# LCmeter0-LCD-8pinlcd.net
KiCad netlist of a schematic drawn in EAGLE
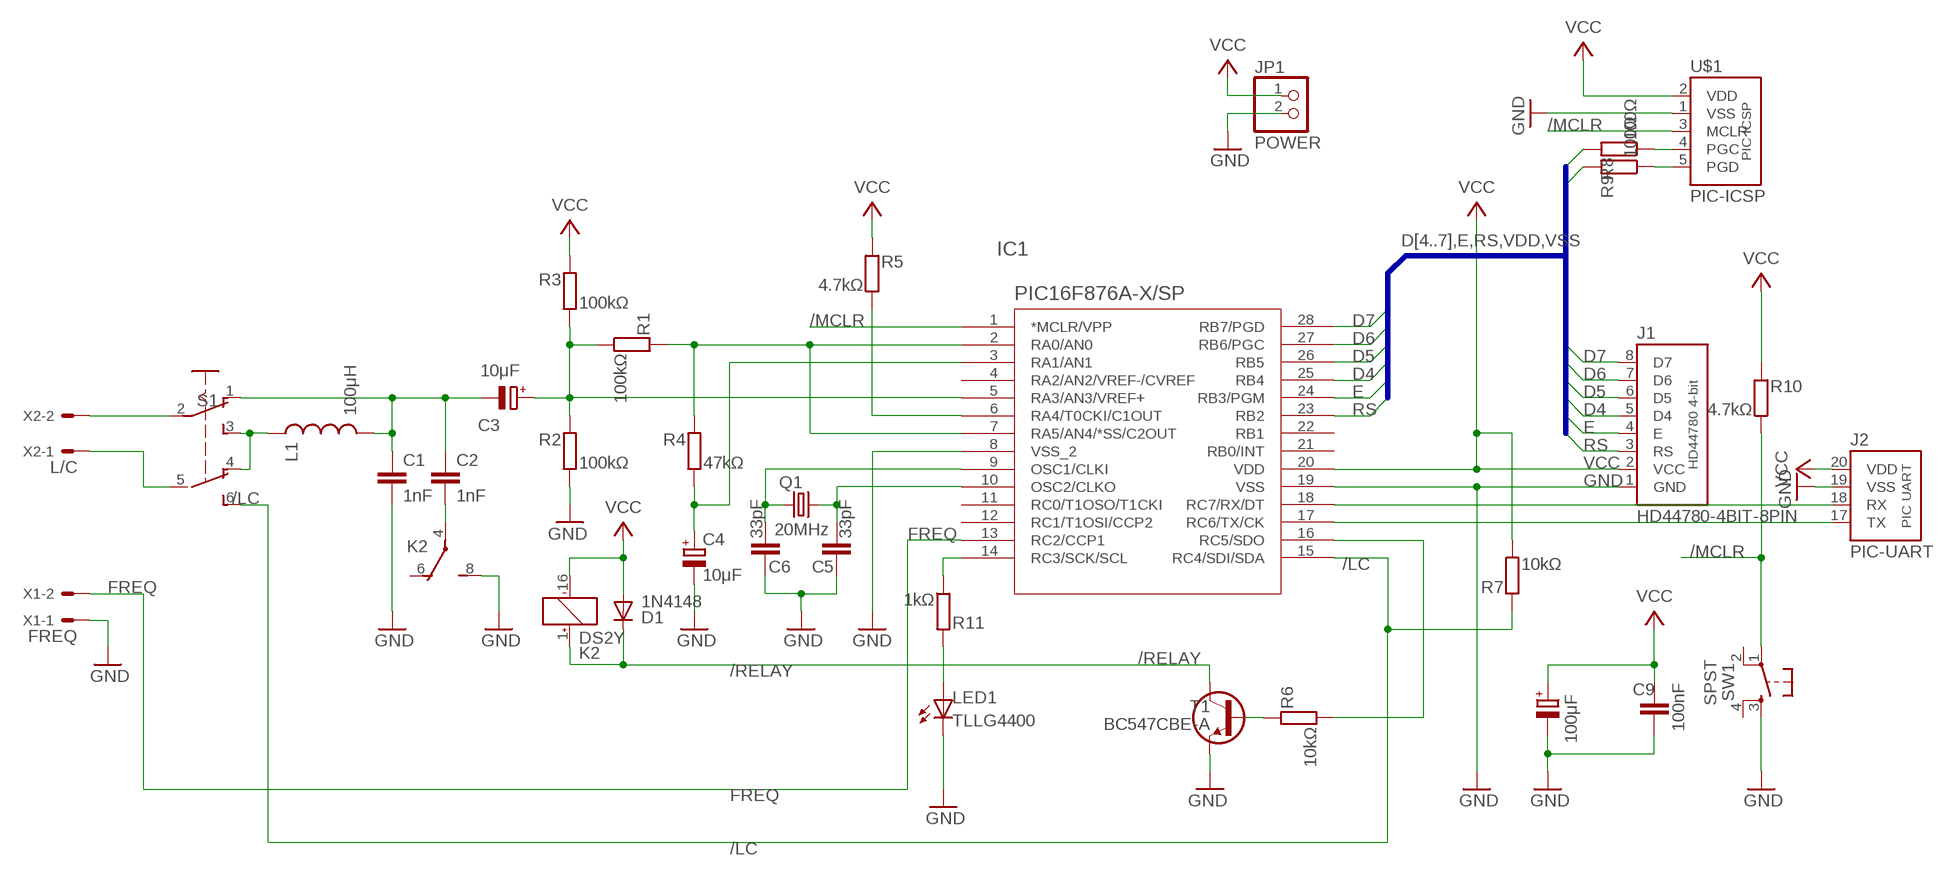
[diagram p0: schematic, sheet 1]

(export (version "E")
  (design (tool "Eeschema 10.0.6"))
  (components
    (comp (ref "C1")
      (value "1nF")
      (footprint "eagle-import:C050-020X036")
      (libsource (lib "eagle-import") (part "C050-020X036"))
    )
    (comp (ref "C2")
      (value "1nF")
      (footprint "eagle-import:C050-020X036")
      (libsource (lib "eagle-import") (part "C050-020X036"))
    )
    (comp (ref "C3")
      (value "10μF")
      (footprint "eagle-import:E5-4")
      (libsource (lib "eagle-import") (part "CPOLE5-4"))
    )
    (comp (ref "C4")
      (value "10μF")
      (footprint "eagle-import:E5-4")
      (libsource (lib "eagle-import") (part "CPOLE5-4"))
    )
    (comp (ref "C5")
      (value "33pF")
      (footprint "eagle-import:C025-020X036")
      (libsource (lib "eagle-import") (part "C025-020X036"))
    )
    (comp (ref "C6")
      (value "33pF")
      (footprint "eagle-import:C025-020X036")
      (libsource (lib "eagle-import") (part "C025-020X036"))
    )
    (comp (ref "C7")
      (value "100μF")
      (footprint "eagle-import:E2,5-6")
      (libsource (lib "eagle-import") (part "CPOLE2.5-6"))
    )
    (comp (ref "C9")
      (value "100nF")
      (footprint "eagle-import:C025-024X044")
      (libsource (lib "eagle-import") (part "C-EU025-024X044"))
    )
    (comp (ref "D1")
      (value "1N4148")
      (footprint "eagle-import:DO34-7")
      (libsource (lib "eagle-import") (part "1N414834-7"))
    )
    (comp (ref "IC1")
      (value "PIC16F876A-X/SP")
      (footprint "eagle-import:DIL28-3")
      (libsource (lib "eagle-import") (part "PIC16F876A-X/SP"))
    )
    (comp (ref "J1")
      (value "HD44780-4BIT-8PIN")
      (footprint "eagle-import:CONN-8P")
      (libsource (lib "eagle-import") (part "HD44780-4BIT-8PIN"))
    )
    (comp (ref "J2")
      (value "PIC-UART")
      (footprint "eagle-import:PIC-UART")
      (libsource (lib "eagle-import") (part "PIC-UART"))
    )
    (comp (ref "JP1")
      (value "POWER")
      (footprint "eagle-import:1X02")
      (libsource (lib "eagle-import") (part "PINHD-1X2"))
    )
    (comp (ref "K2")
      (value "DS2Y")
      (footprint "eagle-import:DS2Y")
      (fields (field (name "MPN") "DS2Y-S-DC5V"))
      (libsource (lib "eagle-import") (part "DS2Y-S-DC5V"))
    )
    (comp (ref "L1")
      (value "100μH")
      (footprint "eagle-import:L-02_7")
      (libsource (lib "eagle-import") (part "L02/7"))
    )
    (comp (ref "LED1")
      (value "TLLG4400")
      (footprint "eagle-import:LED3MM")
      (fields (field (name "MF") "VISHAY SEMICONDUCTOR"))
      (libsource (lib "eagle-import") (part "TLLG4400"))
    )
    (comp (ref "Q1")
      (value "20MHz")
      (footprint "eagle-import:HC49")
      (libsource (lib "eagle-import") (part "CRYSTALHC49"))
    )
    (comp (ref "R1")
      (value "100kΩ")
      (footprint "eagle-import:0202_2V")
      (libsource (lib "eagle-import") (part "R0202/2V"))
    )
    (comp (ref "R2")
      (value "100kΩ")
      (footprint "eagle-import:0202_7")
      (libsource (lib "eagle-import") (part "R0202/7"))
    )
    (comp (ref "R3")
      (value "100kΩ")
      (footprint "eagle-import:0202_2V")
      (libsource (lib "eagle-import") (part "R0202/2V"))
    )
    (comp (ref "R4")
      (value "47kΩ")
      (footprint "eagle-import:0202_2V")
      (libsource (lib "eagle-import") (part "R0202/2V"))
    )
    (comp (ref "R5")
      (value "4.7kΩ")
      (footprint "eagle-import:0202_7")
      (libsource (lib "eagle-import") (part "R0202/7"))
    )
    (comp (ref "R6")
      (value "10kΩ")
      (footprint "eagle-import:0202_7")
      (libsource (lib "eagle-import") (part "R0202/7"))
    )
    (comp (ref "R7")
      (value "10kΩ")
      (footprint "eagle-import:0202_10")
      (libsource (lib "eagle-import") (part "R0202/10"))
    )
    (comp (ref "R8")
      (value "100Ω")
      (footprint "eagle-import:0202_5")
      (libsource (lib "eagle-import") (part "R0202/5"))
    )
    (comp (ref "R9")
      (value "100Ω")
      (footprint "eagle-import:0202_5")
      (libsource (lib "eagle-import") (part "R0202/5"))
    )
    (comp (ref "R10")
      (value "4.7kΩ")
      (footprint "eagle-import:0202_2V")
      (libsource (lib "eagle-import") (part "R0202/2V"))
    )
    (comp (ref "R11")
      (value "1kΩ")
      (footprint "eagle-import:0202_5")
      (libsource (lib "eagle-import") (part "R0202/5"))
    )
    (comp (ref "S1")
      (value "SL-SW-2P-2T")
      (footprint "eagle-import:SLSW-2P2T")
      (libsource (lib "eagle-import") (part "SL-SW-2P-2T"))
    )
    (comp (ref "SW1")
      (value "SPST")
      (footprint "eagle-import:PB-5")
      (libsource (lib "eagle-import") (part "PB-SPST"))
    )
    (comp (ref "T1")
      (value "BC547CBE-A")
      (footprint "eagle-import:TO92-CBE-A")
      (libsource (lib "eagle-import") (part "BC547CBE-A"))
    )
    (comp (ref "U$1")
      (value "PIC-ICSP")
      (footprint "eagle-import:CONN-5P")
      (libsource (lib "eagle-import") (part "PIC-ICSP"))
    )
    (comp (ref "X1")
      (value "FREQ")
      (footprint "eagle-import:70543-02")
      (libsource (lib "eagle-import") (part "C-GRID-02-70543"))
    )
    (comp (ref "X2")
      (value "L/C")
      (footprint "eagle-import:70543-02")
      (libsource (lib "eagle-import") (part "C-GRID-02-70543"))
    )
  )
  (nets
    (net (code "3") (name "/D4") (class "Default")
      (node (ref "IC1") (pin "25") (pinfunction "RB4_25") (pintype "passive"))
      (node (ref "J1") (pin "5") (pinfunction "D4_5") (pintype "passive"))
    )
    (net (code "4") (name "/D5") (class "Default")
      (node (ref "IC1") (pin "26") (pinfunction "RB5_26") (pintype "passive"))
      (node (ref "J1") (pin "6") (pinfunction "D5_6") (pintype "passive"))
    )
    (net (code "5") (name "/D6") (class "Default")
      (node (ref "IC1") (pin "27") (pinfunction "RB6/PGC_27") (pintype "passive"))
      (node (ref "J1") (pin "7") (pinfunction "D6_7") (pintype "passive"))
      (node (ref "R9") (pin "2") (pinfunction "2_2") (pintype "passive"))
    )
    (net (code "6") (name "/D7") (class "Default")
      (node (ref "IC1") (pin "28") (pinfunction "RB7/PGD_28") (pintype "passive"))
      (node (ref "J1") (pin "8") (pinfunction "D7_8") (pintype "passive"))
      (node (ref "R8") (pin "2") (pinfunction "2_2") (pintype "passive"))
    )
    (net (code "7") (name "/E") (class "Default")
      (node (ref "IC1") (pin "24") (pinfunction "RB3/PGM_24") (pintype "passive"))
      (node (ref "J1") (pin "4") (pinfunction "E_4") (pintype "passive"))
    )
    (net (code "8") (name "/FREQ") (class "Default")
      (node (ref "IC1") (pin "13") (pinfunction "RC2/CCP1_13") (pintype "passive"))
      (node (ref "X1") (pin "2") (pinfunction "S_2") (pintype "passive"))
    )
    (net (code "9") (name "/RS") (class "Default")
      (node (ref "IC1") (pin "23") (pinfunction "RB2_23") (pintype "passive"))
      (node (ref "J1") (pin "3") (pinfunction "RS_3") (pintype "passive"))
    )
    (net (code "11") (name "/{slash}LC") (class "Default")
      (node (ref "IC1") (pin "15") (pinfunction "RC4/SDI/SDA_15") (pintype "passive"))
      (node (ref "R7") (pin "2") (pinfunction "2_2") (pintype "passive"))
      (node (ref "S1") (pin "6") (pinfunction "S1_6") (pintype "passive"))
    )
    (net (code "12") (name "/{slash}MCLR") (class "Default")
      (node (ref "IC1") (pin "1") (pinfunction "*MCLR/VPP_1") (pintype "passive"))
      (node (ref "R10") (pin "1") (pinfunction "1_1") (pintype "passive"))
      (node (ref "SW1") (pin "1") (pinfunction "P_1") (pintype "passive"))
      (node (ref "U$1") (pin "3") (pinfunction "MCLR_3") (pintype "passive"))
    )
    (net (code "13") (name "/{slash}RELAY") (class "Default")
      (node (ref "D1") (pin "C") (pinfunction "C_C") (pintype "passive"))
      (node (ref "K2") (pin "1") (pinfunction "+_1") (pintype "passive"))
      (node (ref "T1") (pin "C") (pinfunction "C_C") (pintype "passive"))
    )
    (net (code "14") (name "GND") (class "Default")
      (node (ref "C1") (pin "2") (pinfunction "2_2") (pintype "passive"))
      (node (ref "C4") (pin "-") (pinfunction "-_-") (pintype "passive"))
      (node (ref "C5") (pin "1") (pinfunction "1_1") (pintype "passive"))
      (node (ref "C6") (pin "1") (pinfunction "1_1") (pintype "passive"))
      (node (ref "C7") (pin "-") (pinfunction "-_-") (pintype "passive"))
      (node (ref "C9") (pin "2") (pinfunction "2_2") (pintype "passive"))
      (node (ref "IC1") (pin "19") (pinfunction "VSS_19") (pintype "passive"))
      (node (ref "IC1") (pin "8") (pinfunction "VSS_2_8") (pintype "passive"))
      (node (ref "J1") (pin "1") (pinfunction "GND_1") (pintype "passive"))
      (node (ref "J2") (pin "19") (pinfunction "VSS_19") (pintype "passive"))
      (node (ref "JP1") (pin "2") (pinfunction "2_2") (pintype "passive"))
      (node (ref "K2") (pin "8") (pinfunction "S_8") (pintype "passive"))
      (node (ref "LED1") (pin "K") (pinfunction "C_K") (pintype "passive"))
      (node (ref "R2") (pin "1") (pinfunction "1_1") (pintype "passive"))
      (node (ref "SW1") (pin "3") (pinfunction "S_3") (pintype "passive"))
      (node (ref "T1") (pin "E") (pinfunction "E_E") (pintype "passive"))
      (node (ref "U$1") (pin "1") (pinfunction "VSS_1") (pintype "passive"))
      (node (ref "X1") (pin "1") (pinfunction "S_1") (pintype "passive"))
    )
    (net (code "15") (name "Net-(IC1-OSC1{slash}CLKI)") (class "Default")
      (node (ref "C6") (pin "2") (pinfunction "2_2") (pintype "passive"))
      (node (ref "IC1") (pin "9") (pinfunction "OSC1/CLKI_9") (pintype "passive"))
      (node (ref "Q1") (pin "1") (pinfunction "1_1") (pintype "passive"))
    )
    (net (code "16") (name "Net-(IC1-OSC2{slash}CLKO)") (class "Default")
      (node (ref "C5") (pin "2") (pinfunction "2_2") (pintype "passive"))
      (node (ref "IC1") (pin "10") (pinfunction "OSC2/CLKO_10") (pintype "passive"))
      (node (ref "Q1") (pin "2") (pinfunction "2_2") (pintype "passive"))
    )
    (net (code "17") (name "Net-(IC1-RA0{slash}AN0)") (class "Default")
      (node (ref "IC1") (pin "2") (pinfunction "RA0/AN0_2") (pintype "passive"))
      (node (ref "IC1") (pin "7") (pinfunction "RA5/AN4/*SS/C2OUT_7") (pintype "passive"))
      (node (ref "R1") (pin "2") (pinfunction "2_2") (pintype "passive"))
      (node (ref "R4") (pin "2") (pinfunction "2_2") (pintype "passive"))
    )
    (net (code "18") (name "Net-(IC1-RA1{slash}AN1)") (class "Default")
      (node (ref "C4") (pin "+") (pinfunction "+_+") (pintype "passive"))
      (node (ref "IC1") (pin "3") (pinfunction "RA1/AN1_3") (pintype "passive"))
      (node (ref "R4") (pin "1") (pinfunction "1_1") (pintype "passive"))
    )
    (net (code "19") (name "Net-(IC1-RA3{slash}AN3{slash}VREF+)") (class "Default")
      (node (ref "C3") (pin "+") (pinfunction "+_+") (pintype "passive"))
      (node (ref "IC1") (pin "5") (pinfunction "RA3/AN3/VREF+_5") (pintype "passive"))
      (node (ref "R1") (pin "1") (pinfunction "1_1") (pintype "passive"))
      (node (ref "R2") (pin "2") (pinfunction "2_2") (pintype "passive"))
      (node (ref "R3") (pin "1") (pinfunction "1_1") (pintype "passive"))
    )
    (net (code "20") (name "Net-(IC1-RA4{slash}T0CKI{slash}C1OUT)") (class "Default")
      (node (ref "IC1") (pin "6") (pinfunction "RA4/T0CKI/C1OUT_6") (pintype "passive"))
      (node (ref "R5") (pin "1") (pinfunction "1_1") (pintype "passive"))
    )
    (net (code "21") (name "Net-(IC1-RC3{slash}SCK{slash}SCL)") (class "Default")
      (node (ref "IC1") (pin "14") (pinfunction "RC3/SCK/SCL_14") (pintype "passive"))
      (node (ref "R11") (pin "1") (pinfunction "1_1") (pintype "passive"))
    )
    (net (code "22") (name "Net-(IC1-RC5{slash}SDO)") (class "Default")
      (node (ref "IC1") (pin "16") (pinfunction "RC5/SDO_16") (pintype "passive"))
      (node (ref "R6") (pin "1") (pinfunction "1_1") (pintype "passive"))
    )
    (net (code "23") (name "Net-(IC1-RC6{slash}TX{slash}CK)") (class "Default")
      (node (ref "IC1") (pin "17") (pinfunction "RC6/TX/CK_17") (pintype "passive"))
      (node (ref "J2") (pin "17") (pinfunction "TX_17") (pintype "passive"))
    )
    (net (code "24") (name "Net-(IC1-RC7{slash}RX{slash}DT)") (class "Default")
      (node (ref "IC1") (pin "18") (pinfunction "RC7/RX/DT_18") (pintype "passive"))
      (node (ref "J2") (pin "18") (pinfunction "RX_18") (pintype "passive"))
    )
    (net (code "25") (name "Net-(K2B-P)") (class "Default")
      (node (ref "C2") (pin "2") (pinfunction "2_2") (pintype "passive"))
      (node (ref "K2") (pin "4") (pinfunction "P_4") (pintype "passive"))
    )
    (net (code "26") (name "Net-(LED1-PadA)") (class "Default")
      (node (ref "LED1") (pin "A") (pinfunction "A_A") (pintype "passive"))
      (node (ref "R11") (pin "2") (pinfunction "2_2") (pintype "passive"))
    )
    (net (code "27") (name "Net-(R6-Pad2)") (class "Default")
      (node (ref "R6") (pin "2") (pinfunction "2_2") (pintype "passive"))
      (node (ref "T1") (pin "B") (pinfunction "B_B") (pintype "passive"))
    )
    (net (code "28") (name "Net-(S1-O)") (class "Default")
      (node (ref "C1") (pin "1") (pinfunction "1_1") (pintype "passive"))
      (node (ref "C2") (pin "1") (pinfunction "1_1") (pintype "passive"))
      (node (ref "C3") (pin "-") (pinfunction "-_-") (pintype "passive"))
      (node (ref "L1") (pin "2") (pinfunction "2_2") (pintype "passive"))
      (node (ref "S1") (pin "1") (pinfunction "O_1") (pintype "passive"))
    )
    (net (code "29") (name "Net-(S1-O1)") (class "Default")
      (node (ref "L1") (pin "1") (pinfunction "1_1") (pintype "passive"))
      (node (ref "S1") (pin "3") (pinfunction "S_3") (pintype "passive"))
      (node (ref "S1") (pin "4") (pinfunction "O1_4") (pintype "passive"))
    )
    (net (code "30") (name "Net-(S1-P)") (class "Default")
      (node (ref "S1") (pin "2") (pinfunction "P_2") (pintype "passive"))
      (node (ref "X2") (pin "2") (pinfunction "S_2") (pintype "passive"))
    )
    (net (code "31") (name "Net-(S1-P1)") (class "Default")
      (node (ref "S1") (pin "5") (pinfunction "P1_5") (pintype "passive"))
      (node (ref "X2") (pin "1") (pinfunction "S_1") (pintype "passive"))
    )
    (net (code "32") (name "Net-(U$1-PGC)") (class "Default")
      (node (ref "R8") (pin "1") (pinfunction "1_1") (pintype "passive"))
      (node (ref "U$1") (pin "4") (pinfunction "PGC_4") (pintype "passive"))
    )
    (net (code "33") (name "Net-(U$1-PGD)") (class "Default")
      (node (ref "R9") (pin "1") (pinfunction "1_1") (pintype "passive"))
      (node (ref "U$1") (pin "5") (pinfunction "PGD_5") (pintype "passive"))
    )
    (net (code "34") (name "VCC") (class "Default")
      (node (ref "C7") (pin "+") (pinfunction "+_+") (pintype "passive"))
      (node (ref "C9") (pin "1") (pinfunction "1_1") (pintype "passive"))
      (node (ref "D1") (pin "A") (pinfunction "A_A") (pintype "passive"))
      (node (ref "IC1") (pin "20") (pinfunction "VDD_20") (pintype "passive"))
      (node (ref "J1") (pin "2") (pinfunction "VCC_2") (pintype "passive"))
      (node (ref "J2") (pin "20") (pinfunction "VDD_20") (pintype "passive"))
      (node (ref "JP1") (pin "1") (pinfunction "1_1") (pintype "passive"))
      (node (ref "K2") (pin "16") (pinfunction "-_16") (pintype "passive"))
      (node (ref "R10") (pin "2") (pinfunction "2_2") (pintype "passive"))
      (node (ref "R3") (pin "2") (pinfunction "2_2") (pintype "passive"))
      (node (ref "R5") (pin "2") (pinfunction "2_2") (pintype "passive"))
      (node (ref "R7") (pin "1") (pinfunction "1_1") (pintype "passive"))
      (node (ref "U$1") (pin "2") (pinfunction "VDD_2") (pintype "passive"))
    )
    (net (code "35") (name "unconnected-(IC1-RA2{slash}AN2{slash}VREF-{slash}CVREF-Pad4)") (class "Default")
      (node (ref "IC1") (pin "4") (pinfunction "RA2/AN2/VREF-/CVREF_4") (pintype "passive"))
    )
    (net (code "36") (name "unconnected-(IC1-RB0{slash}INT-Pad21)") (class "Default")
      (node (ref "IC1") (pin "21") (pinfunction "RB0/INT_21") (pintype "passive"))
    )
    (net (code "37") (name "unconnected-(IC1-RB1-Pad22)") (class "Default")
      (node (ref "IC1") (pin "22") (pinfunction "RB1_22") (pintype "passive"))
    )
    (net (code "38") (name "unconnected-(IC1-RC0{slash}T1OSO{slash}T1CKI-Pad11)") (class "Default")
      (node (ref "IC1") (pin "11") (pinfunction "RC0/T1OSO/T1CKI_11") (pintype "passive"))
    )
    (net (code "39") (name "unconnected-(IC1-RC1{slash}T1OSI{slash}CCP2-Pad12)") (class "Default")
      (node (ref "IC1") (pin "12") (pinfunction "RC1/T1OSI/CCP2_12") (pintype "passive"))
    )
    (net (code "40") (name "unconnected-(K2B-O-Pad6)") (class "Default")
      (node (ref "K2") (pin "6") (pinfunction "O_6") (pintype "passive"))
    )
    (net (code "41") (name "unconnected-(SW1-P1-Pad2)") (class "Default")
      (node (ref "SW1") (pin "2") (pinfunction "P1_2") (pintype "passive"))
    )
    (net (code "42") (name "unconnected-(SW1-S1-Pad4)") (class "Default")
      (node (ref "SW1") (pin "4") (pinfunction "S1_4") (pintype "passive"))
    )
  )
)
